# 7_PowerManagement.net
KiCad netlist of a schematic drawn in Altium Designer
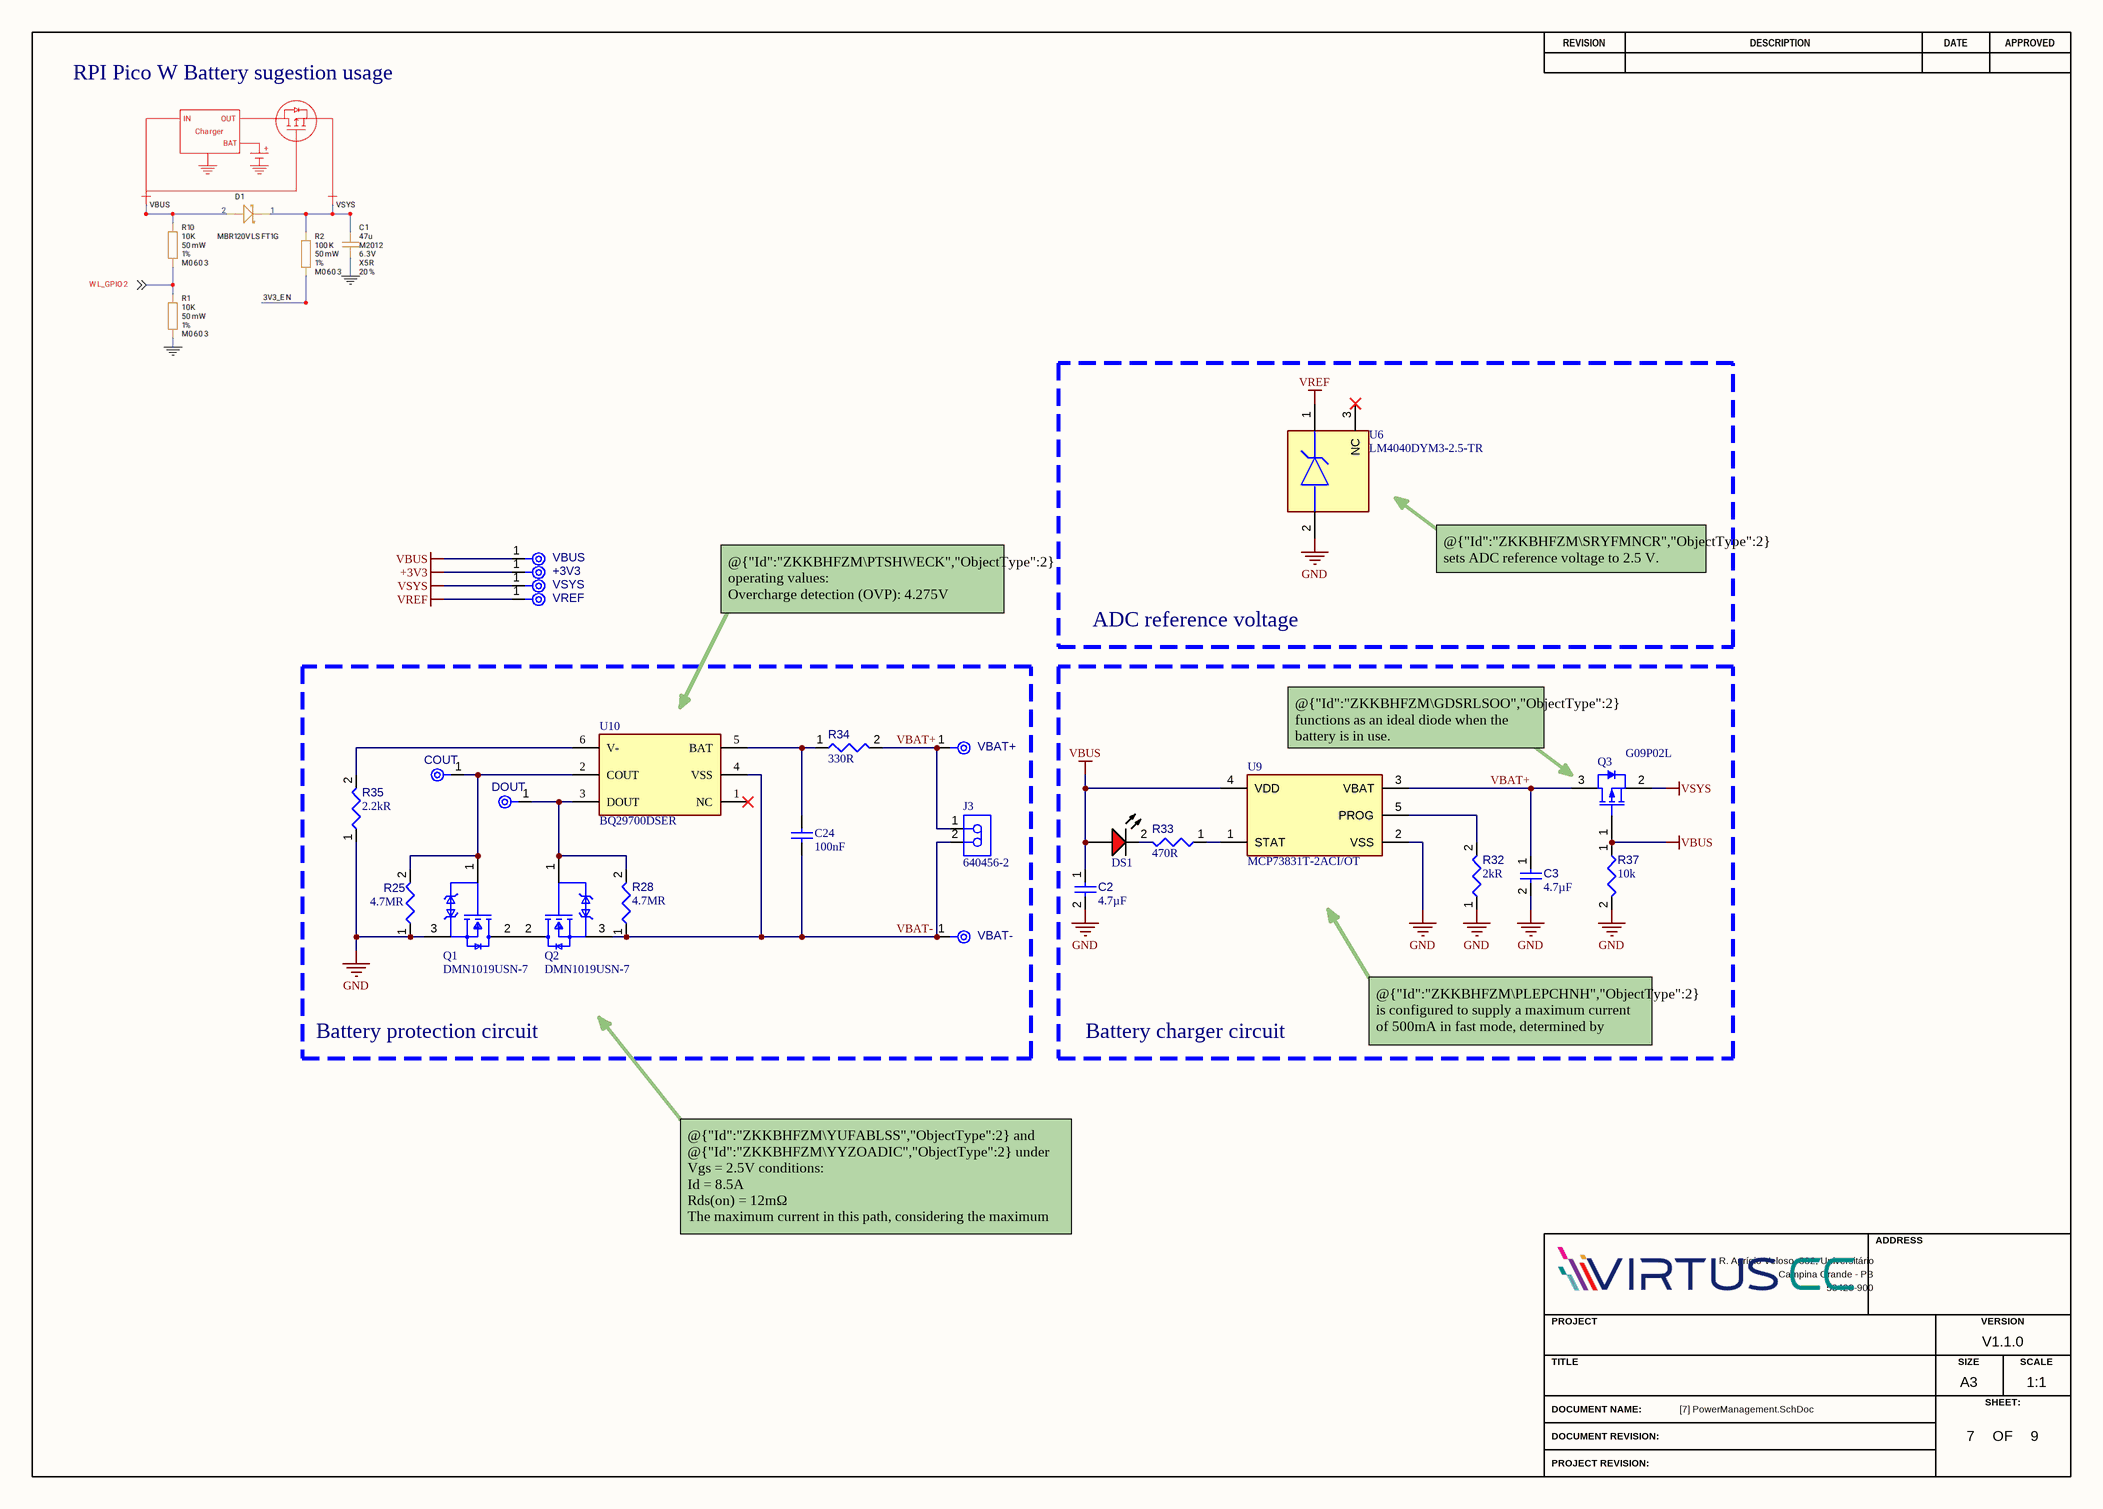
[diagram p0: [7] PowerManagement.SchDoc]

(export (version "E")
  (design (tool "Eeschema 10.0.6"))
  (components
    (comp (ref "+3V3")
      (value "TPAD6R")
      (footprint "TP06R")
      (description "0.6mm round")
      (libsource (lib "UFCG - Universidade Federal de Campina Grande") (part "CMP-001-0001-4"))
    )
    (comp (ref "C2")
      (value "4.7µF")
      (footprint "CAPC0603(1608)100_L")
      (description "Chip Capacitor, 4.7µF +/-20%, 10V, 0603, Thickness 1 mm")
      (fields (field (name "TOLERANCE") "10%") (field (name "Comment") "Capacitor 4.7µF +/-20% 10V 0603"))
      (libsource (lib "UFCG - Universidade Federal de Campina Grande") (part "CAP-NP-2"))
    )
    (comp (ref "C3")
      (value "4.7µF")
      (footprint "CAPC0603(1608)100_L")
      (description "Chip Capacitor, 4.7µF +/-20%, 10V, 0603, Thickness 1 mm")
      (fields (field (name "TOLERANCE") "10%") (field (name "Comment") "Capacitor 4.7µF +/-20% 10V 0603"))
      (libsource (lib "UFCG - Universidade Federal de Campina Grande") (part "CAP-NP-2"))
    )
    (comp (ref "C24")
      (value "100nF")
      (footprint "CAPC0603(1608)100_L")
      (description "Multilayer Ceramic Capacitor, 0.1 uF, 16 V, ± 20%, X7R, 0603 [1608 Metric]")
      (fields (field (name "TOLERANCE") "20%") (field (name "Comment") "VJ0603Y104MXJCW1BC"))
      (libsource (lib "UFCG - Universidade Federal de Campina Grande") (part "CAP"))
    )
    (comp (ref "COUT")
      (value "TPAD6R")
      (footprint "TP06R")
      (description "0.6mm round")
      (libsource (lib "UFCG - Universidade Federal de Campina Grande") (part "CMP-001-0001-4"))
    )
    (comp (ref "DOUT")
      (value "TPAD6R")
      (footprint "TP06R")
      (description "0.6mm round")
      (libsource (lib "UFCG - Universidade Federal de Campina Grande") (part "CMP-001-0001-4"))
    )
    (comp (ref "DS1")
      (value "19-217/R6C-AL1M2VY/3T")
      (footprint "EVRL-0603-2_V")
      (description "Chip LED, Red, 5 V, 25 mA, -40 to 85 degC, 2-Pin SMD (0603), RoHS, Tape and Reel")
      (fields (field (name "MANUFACTURER") "Everlight Electronics"))
      (libsource (lib "UFCG - Universidade Federal de Campina Grande") (part "LED-RED-AK-2"))
    )
    (comp (ref "J3")
      (value "640456-2")
      (footprint "TECO-640456-2_V")
      (description "Connector 250V AC/DC 5A 2P 1 Row PCB - Vertical Mounting Polyester White")
      (libsource (lib "UFCG - Universidade Federal de Campina Grande") (part "CN-2P-F-QF2"))
    )
    (comp (ref "Q1")
      (value "DMN1019USN-7")
      (footprint "FP-SC59-MFG")
      (description "N-Channel 12 V 10 mO 50.6 nC SMT Enhancement Mode Mosfet - SC-59 (SOT-23)")
      (libsource (lib "UFCG - Universidade Federal de Campina Grande") (part "587d6cfc489599008faafaa59ebe43c"))
    )
    (comp (ref "Q2")
      (value "DMN1019USN-7")
      (footprint "FP-SC59-MFG")
      (description "N-Channel 12 V 10 mO 50.6 nC SMT Enhancement Mode Mosfet - SC-59 (SOT-23)")
      (libsource (lib "UFCG - Universidade Federal de Campina Grande") (part "587d6cfc489599008faafaa59ebe43c"))
    )
    (comp (ref "Q3")
      (value "G09P02L")
      (footprint "G09P02L")
      (description "P-Channel Enhancement Mode Power MOSFET")
      (libsource (lib "UFCG - Universidade Federal de Campina Grande") (part "G09P02L"))
    )
    (comp (ref "R25")
      (value "4.7MR")
      (footprint "RESC0603(1608)_L")
      (description "Res Thick Film 0603 4.7M Ohm 5% 0.1W -400ppm/°C to 150ppm/°C Molded SMD Punched Carrier T/R")
      (fields (field (name "TOLERANCE") "5%") (field (name "Comment") "ERJ-3GEYJ475V"))
      (libsource (lib "UFCG - Universidade Federal de Campina Grande") (part "RES-2"))
    )
    (comp (ref "R28")
      (value "4.7MR")
      (footprint "RESC0603(1608)_L")
      (description "Res Thick Film 0603 4.7M Ohm 5% 0.1W -400ppm/°C to 150ppm/°C Molded SMD Punched Carrier T/R")
      (fields (field (name "TOLERANCE") "5%") (field (name "Comment") "ERJ-3GEYJ475V"))
      (libsource (lib "UFCG - Universidade Federal de Campina Grande") (part "RES-2"))
    )
    (comp (ref "R32")
      (value "2kR")
      (footprint "RESC0603(1608)_L")
      (description "SMD Chip Resistor, 2 kOhm, ï¿½ 1%, 100 mW, 0603 [1608 Metric], Thick Film, Precision")
      (fields (field (name "TOLERANCE") "1%") (field (name "Comment") "ERJ-3EKF2001V"))
      (libsource (lib "UFCG - Universidade Federal de Campina Grande") (part "RES-2"))
    )
    (comp (ref "R33")
      (value "470R")
      (footprint "RESC0603(1608)_L")
      (description "Res Thick Film 0603 470 Ohm 5% 0.1W(1/10W) ±200ppm/°C Pad SMD Automotive T/R")
      (fields (field (name "TOLERANCE") "5%") (field (name "Comment") "CRCW0603470RJNEA"))
      (libsource (lib "UFCG - Universidade Federal de Campina Grande") (part "RES-2"))
    )
    (comp (ref "R34")
      (value "330R")
      (footprint "RESC0603(1608)_L")
      (description "SMD Chip Resistor, 330 Ohm, ± 1%, 100 mW, 0603 [1608 Metric], Thick Film, Precision")
      (fields (field (name "TOLERANCE") "1%") (field (name "Comment") "ERJ-3EKF3300V"))
      (libsource (lib "UFCG - Universidade Federal de Campina Grande") (part "RES-2"))
    )
    (comp (ref "R35")
      (value "2.2kR")
      (footprint "RESC0603(1608)_L")
      (description "SMD Chip Resistor, 2.2 kOhm, ± 1%, 100 mW, 0603 [1608 Metric], Thick Film, General Purpose")
      (fields (field (name "TOLERANCE") "1%") (field (name "Comment") "CRCW06032K20FKEA"))
      (libsource (lib "UFCG - Universidade Federal de Campina Grande") (part "RES-2"))
    )
    (comp (ref "R37")
      (value "10k")
      (footprint "RESC0603(1608)_L")
      (description "Chip Resistor, 10 KOhm, +/- 1%, 01 W, -55 to 155 degC, 0603 (1608 Metric)")
      (fields (field (name "POWER") "100mW") (field (name "TOLERANCE") "1%"))
      (libsource (lib "UFCG - Universidade Federal de Campina Grande") (part "RES-2"))
    )
    (comp (ref "U6")
      (value "LM4040DYM3-2.5-TR")
      (footprint "FP-SOT23-3LD-PL-1-IPC_A")
      (description "LM4040 Series 2.5 V ±1 % Precision Micropower Shunt Voltage Reference - SOT-23")
      (fields (field (name "TOLERANCE") "1%"))
      (libsource (lib "UFCG - Universidade Federal de Campina Grande") (part "91f0ca7be5727739b22823fb575e884"))
    )
    (comp (ref "U9")
      (value "MCP73831T-2ACI/OT")
      (footprint "FP-C04-091-OT-MFG")
      (description "MCP73831 Series Single-Cell Li-Ion/Li-Polymer Battery Charge Controller SOT-23-5")
      (libsource (lib "UFCG - Universidade Federal de Campina Grande") (part "61f5a3bb3429d9e0caadea342aa3b19"))
    )
    (comp (ref "U10")
      (value "BQ29700DSER")
      (footprint "FP-DSE0006A-MFG")
      (description "Li-Ion/Li Polymer Advanced Single-Cell Battery Protector IC Family 6-WSON -40 to 85")
      (libsource (lib "UFCG - Universidade Federal de Campina Grande") (part "cb1a035e2e9bf15fad579f9d3aca51e"))
    )
    (comp (ref "VBAT+")
      (value "TPAD6R")
      (footprint "TP06R")
      (description "0.6mm round")
      (libsource (lib "UFCG - Universidade Federal de Campina Grande") (part "CMP-001-0001-4"))
    )
    (comp (ref "VBAT-")
      (value "TPAD6R")
      (footprint "TP06R")
      (description "0.6mm round")
      (libsource (lib "UFCG - Universidade Federal de Campina Grande") (part "CMP-001-0001-4"))
    )
    (comp (ref "VBUS")
      (value "TPAD6R")
      (footprint "TP06R")
      (description "0.6mm round")
      (libsource (lib "UFCG - Universidade Federal de Campina Grande") (part "CMP-001-0001-4"))
    )
    (comp (ref "VREF")
      (value "TPAD6R")
      (footprint "TP06R")
      (description "0.6mm round")
      (libsource (lib "UFCG - Universidade Federal de Campina Grande") (part "CMP-001-0001-4"))
    )
    (comp (ref "VSYS")
      (value "TPAD6R")
      (footprint "TP06R")
      (description "0.6mm round")
      (libsource (lib "UFCG - Universidade Federal de Campina Grande") (part "CMP-001-0001-4"))
    )
  )
  (nets
    (net (code "1") (name "+3V3") (class "Default")
      (node (ref "+3V3") (pin "1") (pinfunction "TP_1") (pintype "passive"))
    )
    (net (code "2") (name "/VBAT+") (class "Default")
      (node (ref "C3") (pin "1") (pinfunction "1_1") (pintype "passive"))
      (node (ref "J3") (pin "1") (pinfunction "1_1") (pintype "passive"))
      (node (ref "Q3") (pin "3") (pinfunction "D_3") (pintype "passive"))
      (node (ref "R34") (pin "2") (pinfunction "2_2") (pintype "passive"))
      (node (ref "U9") (pin "3") (pinfunction "VBAT_3") (pintype "power_in"))
      (node (ref "VBAT+") (pin "1") (pinfunction "TP_1") (pintype "passive"))
    )
    (net (code "3") (name "/VBAT-") (class "Default")
      (node (ref "C24") (pin "1") (pinfunction "1_1") (pintype "passive"))
      (node (ref "J3") (pin "2") (pinfunction "2_2") (pintype "passive"))
      (node (ref "Q2") (pin "3") (pinfunction "D_3") (pintype "passive"))
      (node (ref "R28") (pin "1") (pinfunction "1_1") (pintype "passive"))
      (node (ref "U10") (pin "4") (pinfunction "VSS_4") (pintype "power_in"))
      (node (ref "VBAT-") (pin "1") (pinfunction "TP_1") (pintype "passive"))
    )
    (net (code "4") (name "GND") (class "Default")
      (node (ref "C2") (pin "2") (pinfunction "2_2") (pintype "passive"))
      (node (ref "C3") (pin "2") (pinfunction "2_2") (pintype "passive"))
      (node (ref "Q1") (pin "3") (pinfunction "D_3") (pintype "passive"))
      (node (ref "R25") (pin "1") (pinfunction "1_1") (pintype "passive"))
      (node (ref "R32") (pin "1") (pinfunction "1_1") (pintype "passive"))
      (node (ref "R35") (pin "1") (pinfunction "1_1") (pintype "passive"))
      (node (ref "R37") (pin "2") (pinfunction "2_2") (pintype "passive"))
      (node (ref "U6") (pin "2") (pinfunction "-_2") (pintype "passive"))
      (node (ref "U9") (pin "2") (pinfunction "VSS_2") (pintype "power_in"))
    )
    (net (code "5") (name "Net-(COUT-TP)") (class "Default")
      (node (ref "COUT") (pin "1") (pinfunction "TP_1") (pintype "passive"))
      (node (ref "Q1") (pin "1") (pinfunction "G_1") (pintype "passive"))
      (node (ref "R25") (pin "2") (pinfunction "2_2") (pintype "passive"))
      (node (ref "U10") (pin "2") (pinfunction "COUT_2") (pintype "passive"))
    )
    (net (code "6") (name "Net-(DOUT-TP)") (class "Default")
      (node (ref "DOUT") (pin "1") (pinfunction "TP_1") (pintype "passive"))
      (node (ref "Q2") (pin "1") (pinfunction "G_1") (pintype "passive"))
      (node (ref "R28") (pin "2") (pinfunction "2_2") (pintype "passive"))
      (node (ref "U10") (pin "3") (pinfunction "DOUT_3") (pintype "passive"))
    )
    (net (code "7") (name "Net-(DS1-K)") (class "Default")
      (node (ref "DS1") (pin "2") (pinfunction "K_2") (pintype "passive"))
      (node (ref "R33") (pin "2") (pinfunction "2_2") (pintype "passive"))
    )
    (net (code "8") (name "Net-(Q1-S)") (class "Default")
      (node (ref "Q1") (pin "2") (pinfunction "S_2") (pintype "passive"))
      (node (ref "Q2") (pin "2") (pinfunction "S_2") (pintype "passive"))
    )
    (net (code "9") (name "Net-(U9-PROG)") (class "Default")
      (node (ref "R32") (pin "2") (pinfunction "2_2") (pintype "passive"))
      (node (ref "U9") (pin "5") (pinfunction "PROG_5") (pintype "passive"))
    )
    (net (code "10") (name "Net-(U9-STAT)") (class "Default")
      (node (ref "R33") (pin "1") (pinfunction "1_1") (pintype "passive"))
      (node (ref "U9") (pin "1") (pinfunction "STAT_1") (pintype "passive"))
    )
    (net (code "11") (name "Net-(U10-BAT)") (class "Default")
      (node (ref "C24") (pin "2") (pinfunction "2_2") (pintype "passive"))
      (node (ref "R34") (pin "1") (pinfunction "1_1") (pintype "passive"))
      (node (ref "U10") (pin "5") (pinfunction "BAT_5") (pintype "power_in"))
    )
    (net (code "12") (name "Net-(U10-V-)") (class "Default")
      (node (ref "R35") (pin "2") (pinfunction "2_2") (pintype "passive"))
      (node (ref "U10") (pin "6") (pinfunction "V-_6") (pintype "passive"))
    )
    (net (code "13") (name "VBUS") (class "Default")
      (node (ref "C2") (pin "1") (pinfunction "1_1") (pintype "passive"))
      (node (ref "DS1") (pin "1") (pinfunction "A_1") (pintype "passive"))
      (node (ref "Q3") (pin "1") (pinfunction "G_1") (pintype "passive"))
      (node (ref "R37") (pin "1") (pinfunction "1_1") (pintype "passive"))
      (node (ref "U9") (pin "4") (pinfunction "VDD_4") (pintype "power_in"))
      (node (ref "VBUS") (pin "1") (pinfunction "TP_1") (pintype "passive"))
    )
    (net (code "14") (name "VREF") (class "Default")
      (node (ref "U6") (pin "1") (pinfunction "+_1") (pintype "passive"))
      (node (ref "VREF") (pin "1") (pinfunction "TP_1") (pintype "passive"))
    )
    (net (code "15") (name "VSYS") (class "Default")
      (node (ref "Q3") (pin "2") (pinfunction "S_2") (pintype "passive"))
      (node (ref "VSYS") (pin "1") (pinfunction "TP_1") (pintype "passive"))
    )
    (net (code "16") (name "unconnected-(U6-NC-Pad3)") (class "Default")
      (node (ref "U6") (pin "3") (pinfunction "NC_3") (pintype "passive+no_connect"))
    )
    (net (code "17") (name "unconnected-(U10-NC-Pad1)") (class "Default")
      (node (ref "U10") (pin "1") (pinfunction "NC_1") (pintype "passive+no_connect"))
    )
  )
)
